# USB.net
KiCad netlist of a schematic drawn in EAGLE
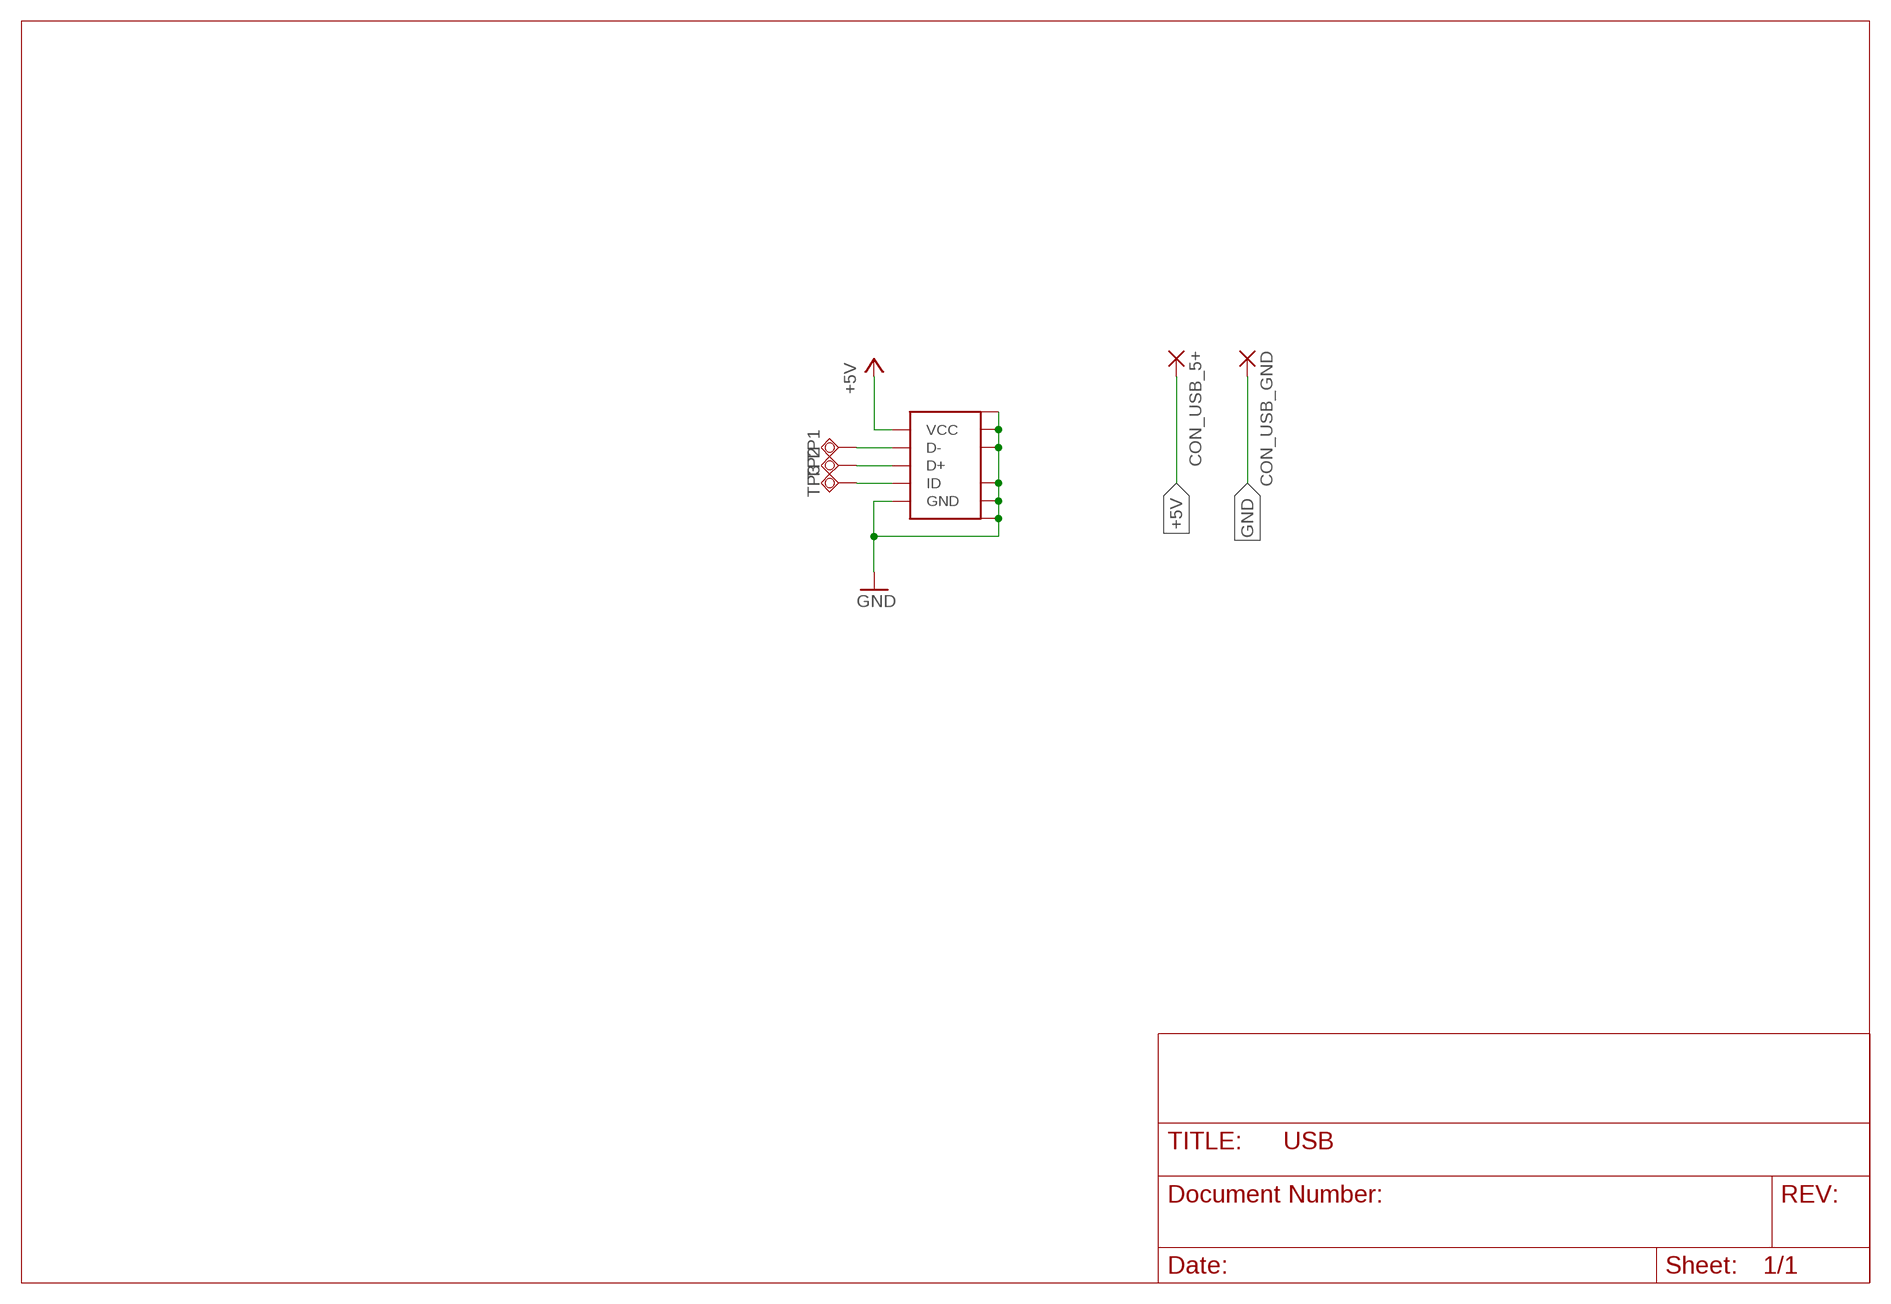
[diagram p0: schematic, sheet 1]

(export (version "E")
  (design (tool "Eeschema 10.0.6"))
  (components
    (comp (ref "CON_USB_5+")
      (value "SMD5")
      (footprint "eagle-import:SMD2,54-5,08")
      (libsource (lib "eagle-import") (part "SMD5"))
    )
    (comp (ref "CON_USB_GND")
      (value "SMD5")
      (footprint "eagle-import:SMD2,54-5,08")
      (libsource (lib "eagle-import") (part "SMD5"))
    )
    (comp (ref "TP1")
      (value "TPSQB1,27")
      (footprint "eagle-import:B1,27")
      (libsource (lib "eagle-import") (part "TPSQB1,27"))
    )
    (comp (ref "TP2")
      (value "TPSQB1,27")
      (footprint "eagle-import:B1,27")
      (libsource (lib "eagle-import") (part "TPSQB1,27"))
    )
    (comp (ref "TP3")
      (value "TPSQB1,27")
      (footprint "eagle-import:B1,27")
      (libsource (lib "eagle-import") (part "TPSQB1,27"))
    )
    (comp (ref "U$5")
      (value "MICRO_USB_B")
      (footprint "eagle-import:MICRO_USB_B")
      (libsource (lib "eagle-import") (part "MICRO_USB_B"))
    )
  )
  (nets
    (net (code "1") (name "+5V") (class "Default")
      (node (ref "CON_USB_5+") (pin "1") (pinfunction "P_1") (pintype "passive"))
      (node (ref "U$5") (pin "1") (pinfunction "VCC_1") (pintype "power_in"))
    )
    (net (code "2") (name "GND") (class "Default")
      (node (ref "CON_USB_GND") (pin "1") (pinfunction "P_1") (pintype "passive"))
      (node (ref "U$5") (pin "5") (pinfunction "GND_5") (pintype "power_in"))
      (node (ref "U$5") (pin "GND1") (pinfunction "GND_GND1") (pintype "power_in"))
      (node (ref "U$5") (pin "GND2") (pinfunction "GND_GND2") (pintype "power_in"))
      (node (ref "U$5") (pin "GND3") (pinfunction "GND_GND3") (pintype "power_in"))
      (node (ref "U$5") (pin "GND4") (pinfunction "GND_GND4") (pintype "power_in"))
      (node (ref "U$5") (pin "GND5") (pinfunction "GND_GND5") (pintype "power_in"))
      (node (ref "U$5") (pin "GND6") (pinfunction "GND_GND6") (pintype "power_in"))
    )
    (net (code "3") (name "Net-(U$5-D+)") (class "Default")
      (node (ref "TP2") (pin "TP") (pinfunction "TP_TP") (pintype "input"))
      (node (ref "U$5") (pin "3") (pinfunction "D+_3") (pintype "bidirectional"))
    )
    (net (code "4") (name "Net-(U$5-D-)") (class "Default")
      (node (ref "TP1") (pin "TP") (pinfunction "TP_TP") (pintype "input"))
      (node (ref "U$5") (pin "2") (pinfunction "D-_2") (pintype "bidirectional"))
    )
    (net (code "5") (name "Net-(U$5-ID)") (class "Default")
      (node (ref "TP3") (pin "TP") (pinfunction "TP_TP") (pintype "input"))
      (node (ref "U$5") (pin "4") (pinfunction "ID_4") (pintype "bidirectional"))
    )
  )
)
